# BMP581.net
KiCad netlist of a schematic drawn in Altium Designer
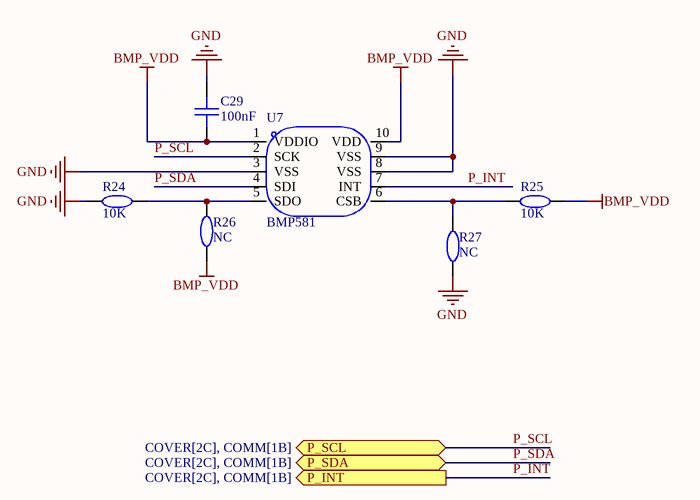
[diagram p0: BMP581.SchDoc]

(export (version "E")
  (design (tool "Eeschema 10.0.6"))
  (components
    (comp (ref "C29")
      (value "100nF")
      (footprint "C0402")
      (fields (field (name "NAME") "100nF"))
      (libsource (lib "my_library") (part "CAP_0402"))
    )
    (comp (ref "R24")
      (value "10K")
      (footprint "R0402")
      (fields (field (name "NAME") "10K"))
      (libsource (lib "my_library") (part "Res_0402"))
    )
    (comp (ref "R25")
      (value "10K")
      (footprint "R0402")
      (fields (field (name "NAME") "10K"))
      (libsource (lib "my_library") (part "Res_0402"))
    )
    (comp (ref "R26")
      (value "NC")
      (footprint "R0402")
      (fields (field (name "NAME") "NC"))
      (libsource (lib "my_library") (part "Res_0402"))
    )
    (comp (ref "R27")
      (value "NC")
      (footprint "R0402")
      (fields (field (name "NAME") "NC"))
      (libsource (lib "my_library") (part "Res_0402"))
    )
    (comp (ref "U7")
      (value "BMP581")
      (footprint "LGA-10_L2.0-W2.0-P0.50-TL_BMP581")
      (fields (field (name "MANUFACTURER") "Bosch(博世)") (field (name "NAME") "BMP581"))
      (libsource (lib "my_library") (part "BMP581"))
    )
  )
  (nets
    (net (code "1") (name "/P_INT") (class "Default")
      (node (ref "U7") (pin "7") (pinfunction "INT_7") (pintype "passive"))
    )
    (net (code "2") (name "/P_SCL") (class "Default")
      (node (ref "U7") (pin "2") (pinfunction "SCK_2") (pintype "passive"))
    )
    (net (code "3") (name "/P_SDA") (class "Default")
      (node (ref "U7") (pin "4") (pinfunction "SDI_4") (pintype "passive"))
    )
    (net (code "4") (name "BMP_VDD") (class "Default")
      (node (ref "C29") (pin "1") (pinfunction "1_1") (pintype "passive"))
      (node (ref "R25") (pin "2") (pinfunction "2_2") (pintype "passive"))
      (node (ref "R26") (pin "1") (pinfunction "1_1") (pintype "passive"))
      (node (ref "U7") (pin "1") (pinfunction "VDDIO_1") (pintype "passive"))
      (node (ref "U7") (pin "10") (pinfunction "VDD_10") (pintype "passive"))
    )
    (net (code "5") (name "GND") (class "Default")
      (node (ref "C29") (pin "2") (pinfunction "2_2") (pintype "passive"))
      (node (ref "R24") (pin "1") (pinfunction "1_1") (pintype "passive"))
      (node (ref "R27") (pin "1") (pinfunction "1_1") (pintype "passive"))
      (node (ref "U7") (pin "3") (pinfunction "VSS_3") (pintype "passive"))
      (node (ref "U7") (pin "8") (pinfunction "VSS_8") (pintype "passive"))
      (node (ref "U7") (pin "9") (pinfunction "VSS_9") (pintype "passive"))
    )
    (net (code "6") (name "Net-(U7-CSB)") (class "Default")
      (node (ref "R25") (pin "1") (pinfunction "1_1") (pintype "passive"))
      (node (ref "R27") (pin "2") (pinfunction "2_2") (pintype "passive"))
      (node (ref "U7") (pin "6") (pinfunction "CSB_6") (pintype "passive"))
    )
    (net (code "7") (name "Net-(U7-SDO)") (class "Default")
      (node (ref "R24") (pin "2") (pinfunction "2_2") (pintype "passive"))
      (node (ref "R26") (pin "2") (pinfunction "2_2") (pintype "passive"))
      (node (ref "U7") (pin "5") (pinfunction "SDO_5") (pintype "passive"))
    )
  )
)
